# Clock.net
KiCad netlist of a schematic drawn in Altium Designer
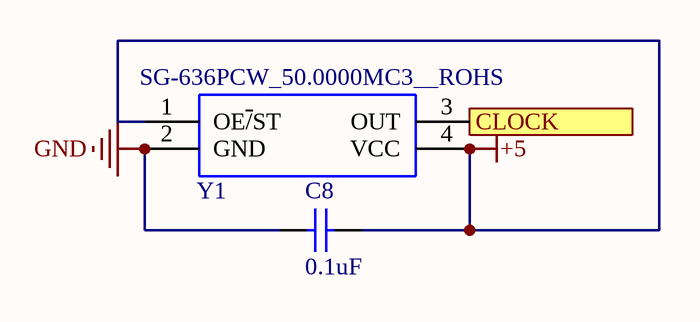
[diagram p0: Clock.SchDoc]

(export (version "E")
  (design (tool "Eeschema 10.0.6"))
  (components
    (comp (ref "C8")
      (value "0.1uF")
      (footprint "CAPC2013X94X50LL20T25")
      (description "Chip Capacitor, 0.1 uF, +/- 5%, 50 V, -55 to 125 degC, 0805 (2012 Metric), RoHS, Tape and Reel")
      (fields (field (name "TOLERANCE") "5%") (field (name "MANUFACTURER") "AVX"))
      (libsource (lib "Altium Content Vault") (part "CAP-NP-2"))
    )
    (comp (ref "Y1")
      (value "SG-636PCW_50.0000MC3__ROHS")
      (footprint "SG-636")
      (description "Standard Clock Oscillators 50MHz 3.3Volt 100ppm -20C +70C")
      (fields (field (name "MANUFACTURER_PART_NUMBER") "SG-636PCW 50.0000MC3: ROHS"))
      (libsource (lib "Husky Robotics Standard Library 2019-2020") (part "SG-636"))
    )
  )
  (nets
    (net (code "1") (name "+5") (class "Default")
      (node (ref "C8") (pin "1") (pinfunction "1_1") (pintype "passive"))
      (node (ref "Y1") (pin "1") (pinfunction "OE~{/}ST_1") (pintype "passive"))
      (node (ref "Y1") (pin "4") (pinfunction "VCC_4") (pintype "power_in"))
    )
    (net (code "2") (name "/CLOCK") (class "Default")
      (node (ref "Y1") (pin "3") (pinfunction "OUT_3") (pintype "passive"))
    )
    (net (code "3") (name "GND") (class "Default")
      (node (ref "C8") (pin "2") (pinfunction "2_2") (pintype "passive"))
      (node (ref "Y1") (pin "2") (pinfunction "GND_2") (pintype "passive"))
    )
  )
)
